# SchemaDriverMoteur.net
KiCad netlist of a schematic drawn in Altium Designer
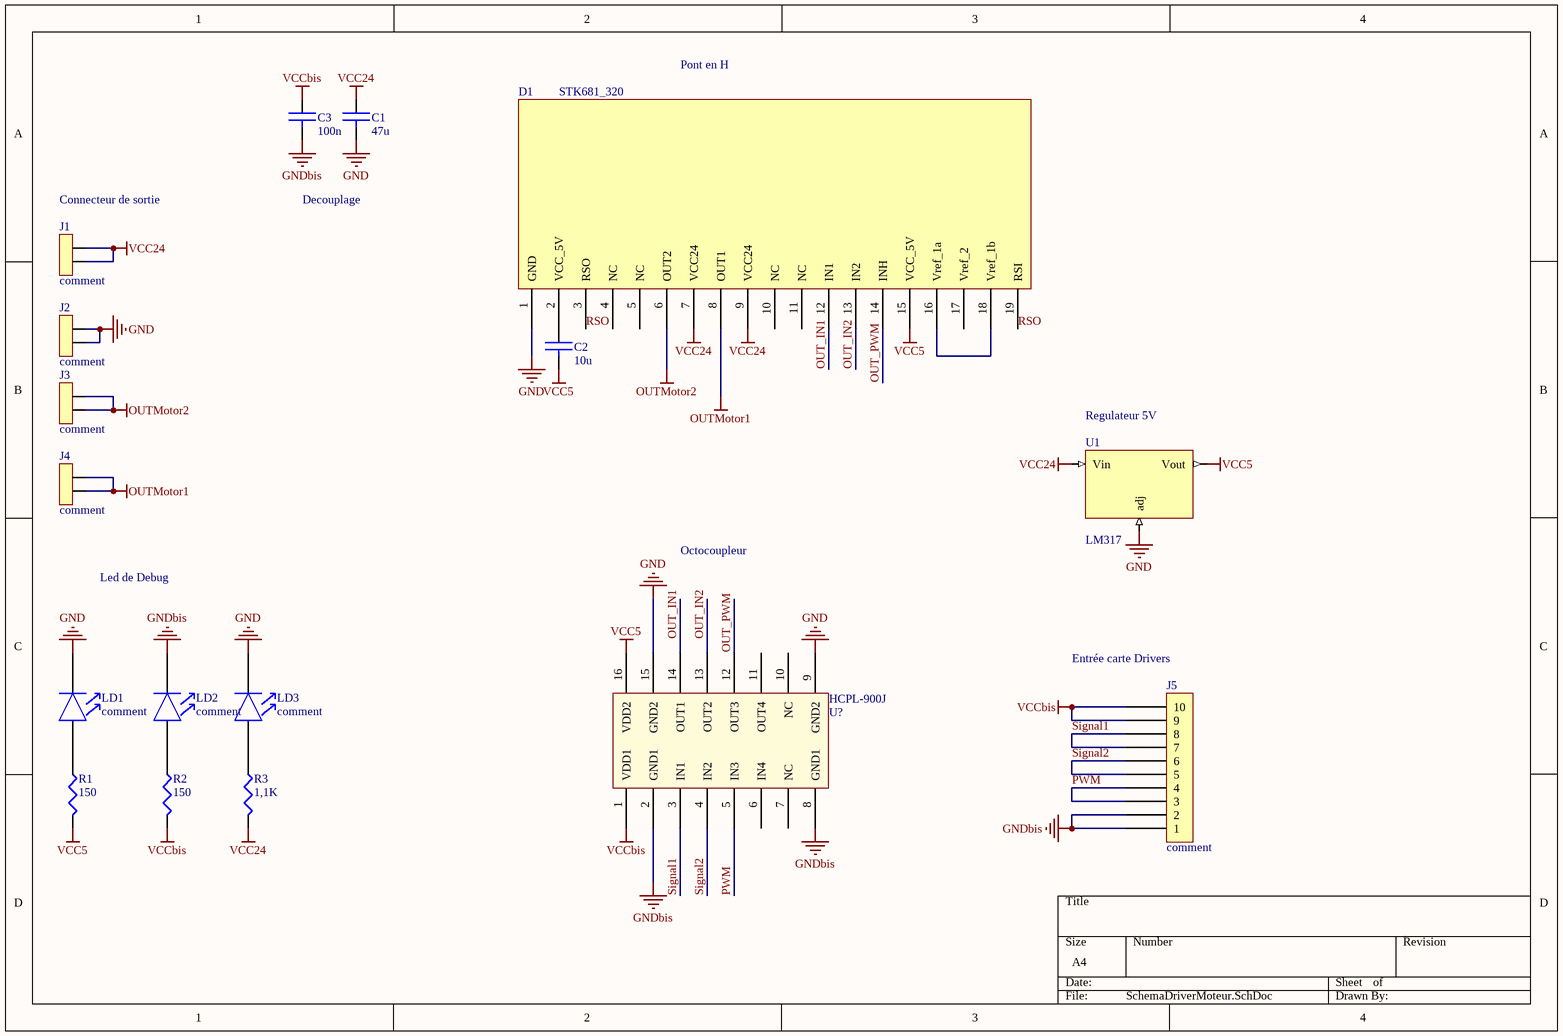
[diagram p0: SchemaDriverMoteur.SchDoc]

(export (version "E")
  (design (tool "Eeschema 10.0.6"))
  (components
    (comp (ref "C1")
      (value "47u")
      (footprint "RAD0.1")
      (description "capacité non polarisée")
      (fields (field (name "Comment") "CAP"))
      (libsource (lib "ISEN_basics") (part "CAP"))
    )
    (comp (ref "C2")
      (value "10u")
      (footprint "RAD0.1")
      (description "capacité non polarisée")
      (fields (field (name "Comment") "CAP"))
      (libsource (lib "ISEN_basics") (part "CAP"))
    )
    (comp (ref "C3")
      (value "100n")
      (footprint "0805")
      (description "capacité non polarisée")
      (fields (field (name "Comment") "CAP"))
      (libsource (lib "ISEN_basics") (part "CAP"))
    )
    (comp (ref "D1")
      (value "STK681_320")
      (footprint "stk681_320")
      (libsource (lib "STK681_320") (part "STK681_320"))
    )
    (comp (ref "HCPL-900J")
      (value "U?")
      (footprint "HCPL-0900j")
      (libsource (lib "HCPL-0900J") (part "HCPL-900J"))
    )
    (comp (ref "J1")
      (value "comment")
      (footprint "AMP_2")
      (description "connecteur alim 2 pôles")
      (libsource (lib "ISEN_basics") (part "POWER2"))
    )
    (comp (ref "J2")
      (value "comment")
      (footprint "AMP_2")
      (description "connecteur alim 2 pôles")
      (libsource (lib "ISEN_basics") (part "POWER2"))
    )
    (comp (ref "J3")
      (value "comment")
      (footprint "AMP_2")
      (description "connecteur alim 2 pôles")
      (libsource (lib "ISEN_basics") (part "POWER2"))
    )
    (comp (ref "J4")
      (value "comment")
      (footprint "AMP_2")
      (description "connecteur alim 2 pôles")
      (libsource (lib "ISEN_basics") (part "POWER2"))
    )
    (comp (ref "J5")
      (value "comment")
      (footprint "HE10-10V")
      (description "10-pin connector")
      (libsource (lib "ISEN_basics") (part "HE10-10"))
    )
    (comp (ref "LD1")
      (value "comment")
      (footprint "LED0805")
      (description "LED 5mm/3mm/CMS")
      (libsource (lib "ISEN_basics") (part "LED"))
    )
    (comp (ref "LD2")
      (value "comment")
      (footprint "LED0805")
      (description "LED 5mm/3mm/CMS")
      (libsource (lib "ISEN_basics") (part "LED"))
    )
    (comp (ref "LD3")
      (value "comment")
      (footprint "LED0805")
      (description "LED 5mm/3mm/CMS")
      (libsource (lib "ISEN_basics") (part "LED"))
    )
    (comp (ref "R1")
      (value "150")
      (footprint "0805")
      (description "resistance")
      (fields (field (name "Comment") "RES"))
      (libsource (lib "ISEN_basics") (part "RES"))
    )
    (comp (ref "R2")
      (value "150")
      (footprint "0805")
      (description "resistance")
      (fields (field (name "Comment") "RES"))
      (libsource (lib "ISEN_basics") (part "RES"))
    )
    (comp (ref "R3")
      (value "1,1K")
      (footprint "0805")
      (description "resistance")
      (fields (field (name "Comment") "RES"))
      (libsource (lib "ISEN_basics") (part "RES"))
    )
    (comp (ref "U1")
      (value "LM317")
      (footprint "TO220V")
      (description "régulateur positif ajustable")
      (libsource (lib "ISEN_basics") (part "REG_ADJ_POS"))
    )
  )
  (nets
    (net (code "1") (name "/OUT_IN1") (class "Default")
      (node (ref "D1") (pin "12") (pinfunction "IN1_12") (pintype "passive"))
      (node (ref "HCPL-900J") (pin "14") (pinfunction "OUT1_14") (pintype "passive"))
    )
    (net (code "2") (name "/OUT_IN2") (class "Default")
      (node (ref "D1") (pin "13") (pinfunction "IN2_13") (pintype "passive"))
      (node (ref "HCPL-900J") (pin "13") (pinfunction "OUT2_13") (pintype "passive"))
    )
    (net (code "3") (name "/OUT_PWM") (class "Default")
      (node (ref "D1") (pin "14") (pinfunction "INH_14") (pintype "passive"))
      (node (ref "HCPL-900J") (pin "12") (pinfunction "OUT3_12") (pintype "passive"))
    )
    (net (code "4") (name "/PWM") (class "Default")
      (node (ref "HCPL-900J") (pin "5") (pinfunction "IN3_5") (pintype "passive"))
      (node (ref "J5") (pin "3") (pinfunction "3_3") (pintype "passive"))
      (node (ref "J5") (pin "4") (pinfunction "4_4") (pintype "passive"))
    )
    (net (code "5") (name "/RSO") (class "Default")
      (node (ref "D1") (pin "19") (pinfunction "RSI_19") (pintype "passive"))
      (node (ref "D1") (pin "3") (pinfunction "RSO_3") (pintype "passive"))
    )
    (net (code "6") (name "/Signal1") (class "Default")
      (node (ref "HCPL-900J") (pin "3") (pinfunction "IN1_3") (pintype "passive"))
      (node (ref "J5") (pin "7") (pinfunction "7_7") (pintype "passive"))
      (node (ref "J5") (pin "8") (pinfunction "8_8") (pintype "passive"))
    )
    (net (code "7") (name "/Signal2") (class "Default")
      (node (ref "HCPL-900J") (pin "4") (pinfunction "IN2_4") (pintype "passive"))
      (node (ref "J5") (pin "5") (pinfunction "5_5") (pintype "passive"))
      (node (ref "J5") (pin "6") (pinfunction "6_6") (pintype "passive"))
    )
    (net (code "8") (name "GND") (class "Default")
      (node (ref "C1") (pin "2") (pinfunction "2_2") (pintype "passive"))
      (node (ref "D1") (pin "1") (pinfunction "GND_1") (pintype "passive"))
      (node (ref "HCPL-900J") (pin "15") (pinfunction "GND2_15") (pintype "power_in"))
      (node (ref "HCPL-900J") (pin "9") (pinfunction "GND2_9") (pintype "power_in"))
      (node (ref "J2") (pin "1") (pintype "passive"))
      (node (ref "J2") (pin "2") (pintype "passive"))
      (node (ref "LD1") (pin "K") (pinfunction "10_K") (pintype "passive"))
      (node (ref "LD3") (pin "K") (pinfunction "10_K") (pintype "passive"))
      (node (ref "U1") (pin "1") (pinfunction "adj_1") (pintype "input"))
    )
    (net (code "9") (name "GNDbis") (class "Default")
      (node (ref "C3") (pin "2") (pinfunction "2_2") (pintype "passive"))
      (node (ref "HCPL-900J") (pin "2") (pinfunction "GND1_2") (pintype "power_in"))
      (node (ref "HCPL-900J") (pin "8") (pinfunction "GND1_8") (pintype "power_in"))
      (node (ref "J5") (pin "1") (pinfunction "1_1") (pintype "passive"))
      (node (ref "J5") (pin "2") (pinfunction "2_2") (pintype "passive"))
      (node (ref "LD2") (pin "K") (pinfunction "10_K") (pintype "passive"))
    )
    (net (code "10") (name "Net-(C2-Pad1)") (class "Default")
      (node (ref "C2") (pin "1") (pinfunction "1_1") (pintype "passive"))
      (node (ref "D1") (pin "2") (pinfunction "VCC_5V_2") (pintype "passive"))
    )
    (net (code "11") (name "Net-(D1-Vref_1a)") (class "Default")
      (node (ref "D1") (pin "16") (pinfunction "Vref_1a_16") (pintype "passive"))
      (node (ref "D1") (pin "18") (pinfunction "Vref_1b_18") (pintype "passive"))
    )
    (net (code "12") (name "Net-(LD1-8)") (class "Default")
      (node (ref "LD1") (pin "A") (pinfunction "8_A") (pintype "passive"))
      (node (ref "R1") (pin "1") (pintype "passive"))
    )
    (net (code "13") (name "Net-(LD2-8)") (class "Default")
      (node (ref "LD2") (pin "A") (pinfunction "8_A") (pintype "passive"))
      (node (ref "R2") (pin "1") (pintype "passive"))
    )
    (net (code "14") (name "Net-(LD3-8)") (class "Default")
      (node (ref "LD3") (pin "A") (pinfunction "8_A") (pintype "passive"))
      (node (ref "R3") (pin "1") (pintype "passive"))
    )
    (net (code "15") (name "OUTMotor1") (class "Default")
      (node (ref "D1") (pin "8") (pinfunction "OUT1_8") (pintype "passive"))
      (node (ref "J4") (pin "1") (pintype "passive"))
      (node (ref "J4") (pin "2") (pintype "passive"))
    )
    (net (code "16") (name "OUTMotor2") (class "Default")
      (node (ref "D1") (pin "6") (pinfunction "OUT2_6") (pintype "passive"))
      (node (ref "J3") (pin "1") (pintype "passive"))
      (node (ref "J3") (pin "2") (pintype "passive"))
    )
    (net (code "17") (name "VCC5") (class "Default")
      (node (ref "C2") (pin "2") (pinfunction "2_2") (pintype "passive"))
      (node (ref "D1") (pin "15") (pinfunction "VCC_5V_15") (pintype "passive"))
      (node (ref "HCPL-900J") (pin "16") (pinfunction "VDD2_16") (pintype "power_in"))
      (node (ref "R1") (pin "2") (pintype "passive"))
      (node (ref "U1") (pin "2") (pinfunction "Vout_2") (pintype "output"))
    )
    (net (code "18") (name "VCC24") (class "Default")
      (node (ref "C1") (pin "1") (pinfunction "1_1") (pintype "passive"))
      (node (ref "D1") (pin "7") (pinfunction "VCC24_7") (pintype "passive"))
      (node (ref "D1") (pin "9") (pinfunction "VCC24_9") (pintype "passive"))
      (node (ref "J1") (pin "1") (pintype "passive"))
      (node (ref "J1") (pin "2") (pintype "passive"))
      (node (ref "R3") (pin "2") (pintype "passive"))
      (node (ref "U1") (pin "3") (pinfunction "Vin_3") (pintype "input"))
    )
    (net (code "19") (name "VCCbis") (class "Default")
      (node (ref "C3") (pin "1") (pinfunction "1_1") (pintype "passive"))
      (node (ref "HCPL-900J") (pin "1") (pinfunction "VDD1_1") (pintype "power_in"))
      (node (ref "J5") (pin "10") (pinfunction "10_10") (pintype "passive"))
      (node (ref "J5") (pin "9") (pinfunction "9_9") (pintype "passive"))
      (node (ref "R2") (pin "2") (pintype "passive"))
    )
    (net (code "20") (name "unconnected-(D1-NC-Pad4)") (class "Default")
      (node (ref "D1") (pin "4") (pinfunction "NC_4") (pintype "passive"))
    )
    (net (code "21") (name "unconnected-(D1-NC-Pad5)") (class "Default")
      (node (ref "D1") (pin "5") (pinfunction "NC_5") (pintype "passive"))
    )
    (net (code "22") (name "unconnected-(D1-NC-Pad10)") (class "Default")
      (node (ref "D1") (pin "10") (pinfunction "NC_10") (pintype "passive"))
    )
    (net (code "23") (name "unconnected-(D1-NC-Pad11)") (class "Default")
      (node (ref "D1") (pin "11") (pinfunction "NC_11") (pintype "passive"))
    )
    (net (code "24") (name "unconnected-(D1-Vref_2-Pad17)") (class "Default")
      (node (ref "D1") (pin "17") (pinfunction "Vref_2_17") (pintype "passive"))
    )
    (net (code "25") (name "unconnected-(HCPL-900J-IN4-Pad6)") (class "Default")
      (node (ref "HCPL-900J") (pin "6") (pinfunction "IN4_6") (pintype "passive"))
    )
    (net (code "26") (name "unconnected-(HCPL-900J-NC-Pad7)") (class "Default")
      (node (ref "HCPL-900J") (pin "7") (pinfunction "NC_7") (pintype "passive"))
    )
    (net (code "27") (name "unconnected-(HCPL-900J-NC-Pad10)") (class "Default")
      (node (ref "HCPL-900J") (pin "10") (pinfunction "NC_10") (pintype "passive"))
    )
    (net (code "28") (name "unconnected-(HCPL-900J-OUT4-Pad11)") (class "Default")
      (node (ref "HCPL-900J") (pin "11") (pinfunction "OUT4_11") (pintype "passive"))
    )
  )
)
